# pcb_v1.net
KiCad netlist of a schematic drawn in Altium Designer
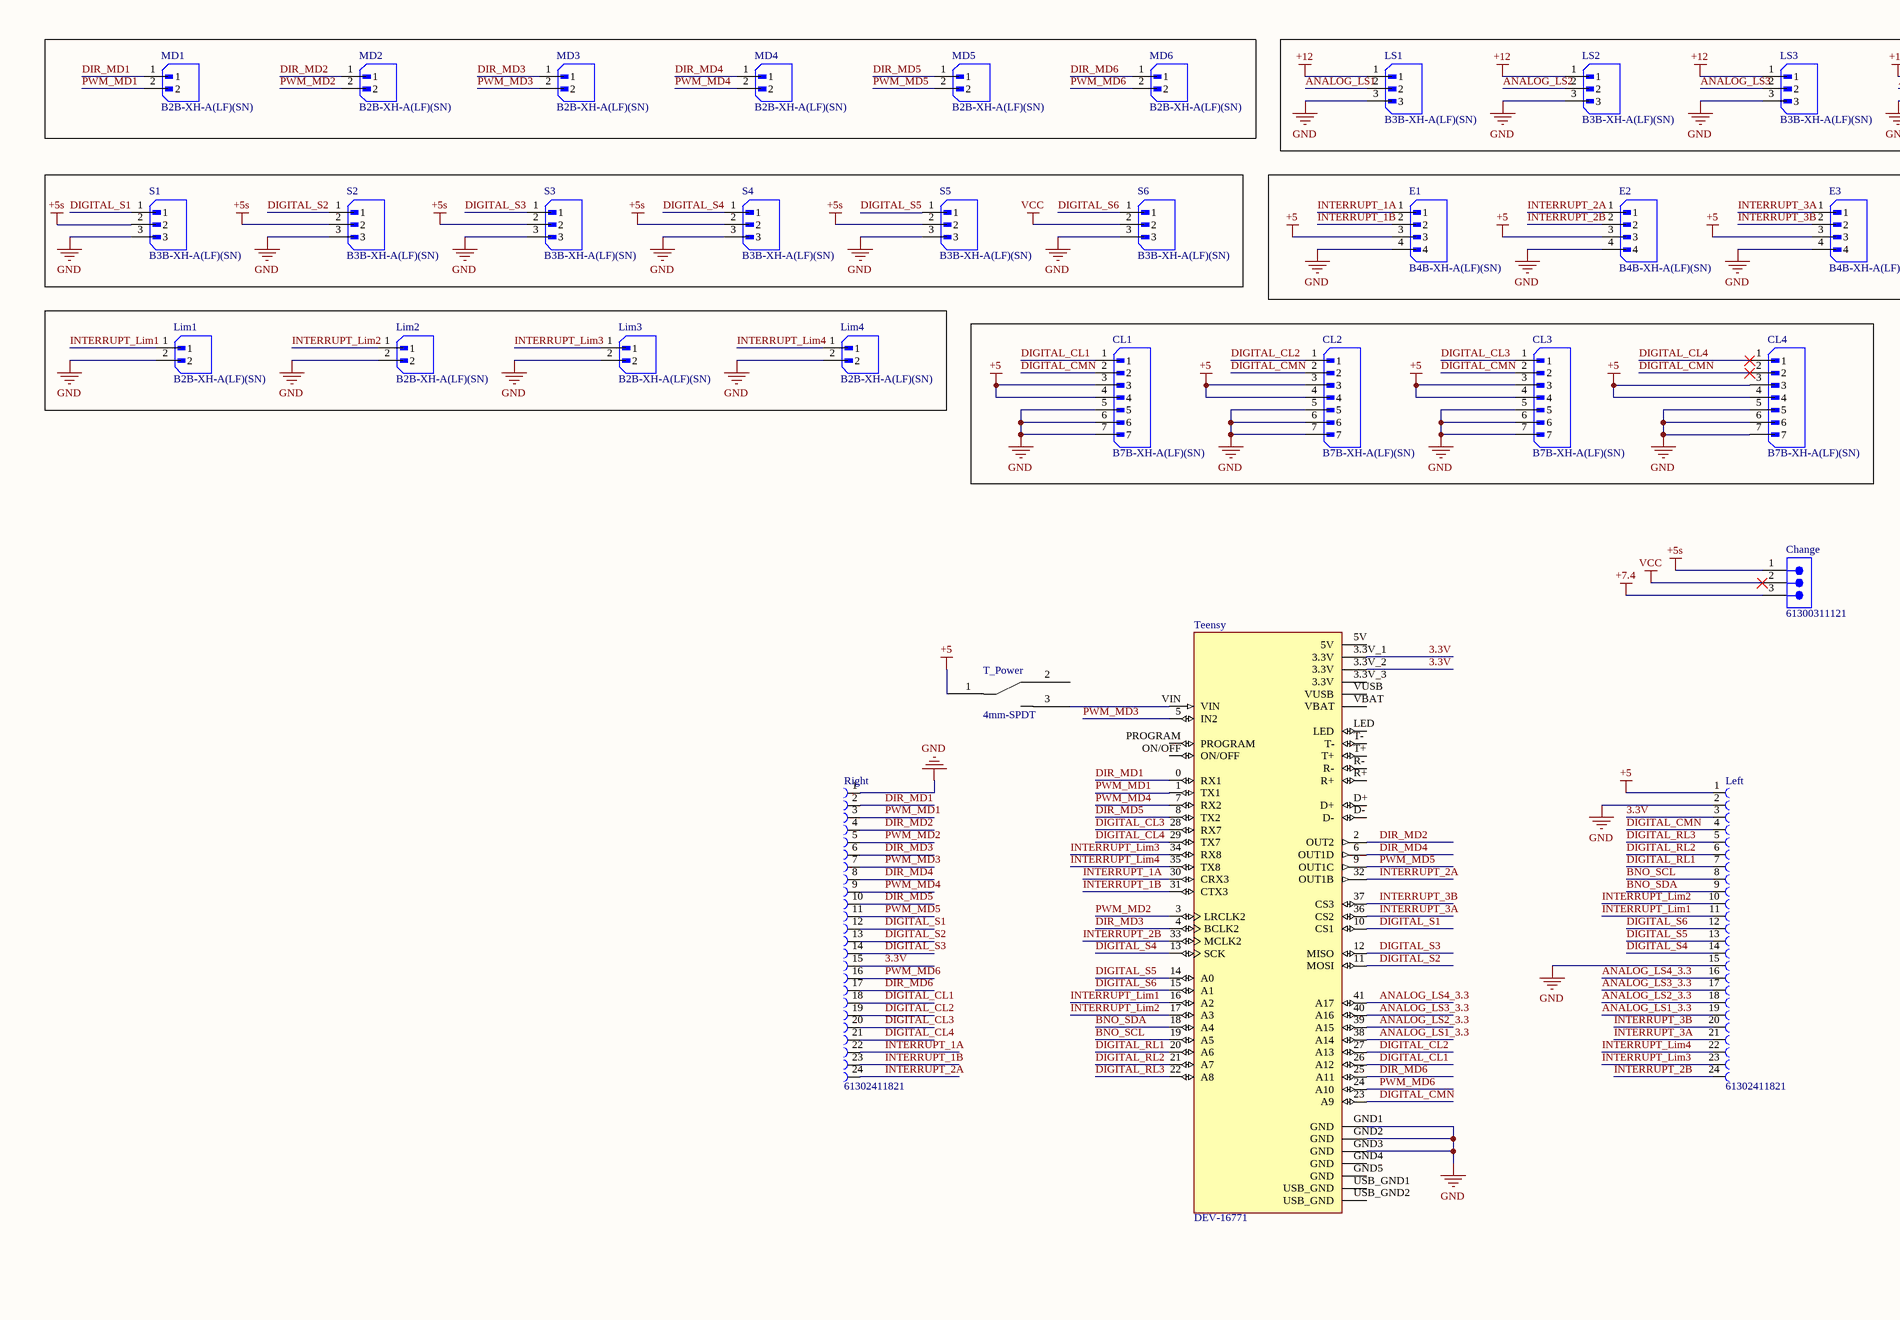
[diagram p0: pcb_v1.SchDoc, left]
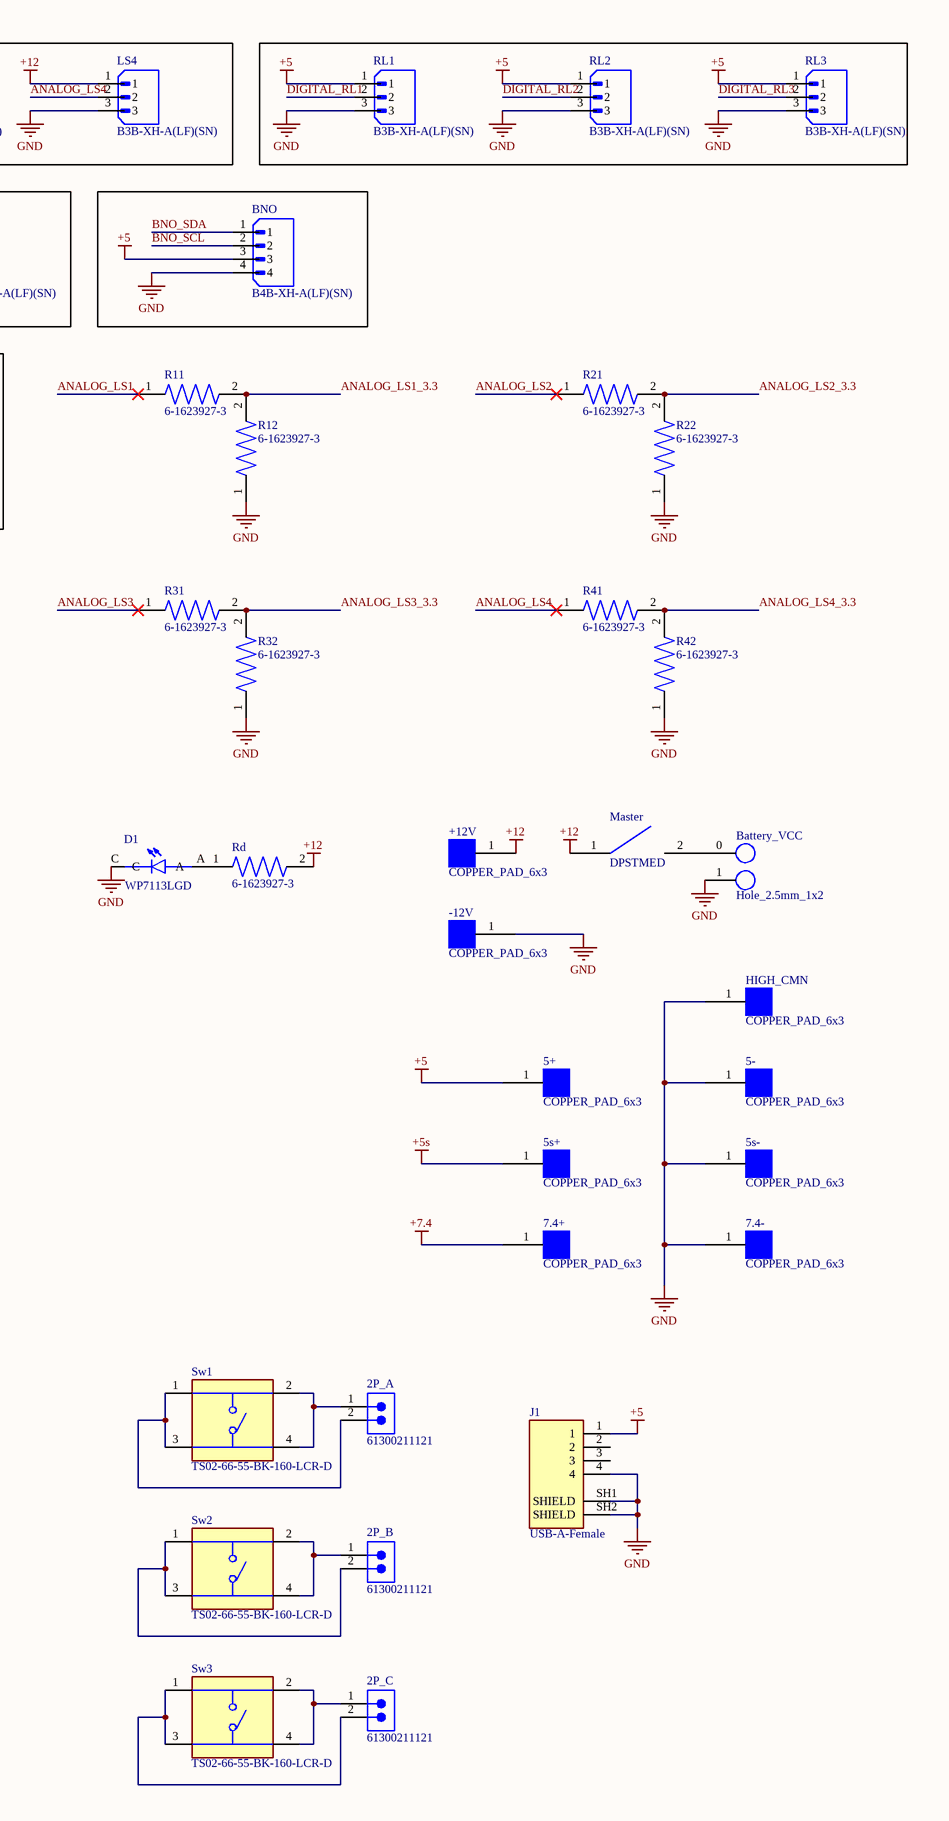
[diagram p1: pcb_v1.SchDoc, right]

(export (version "E")
  (design (tool "Eeschema 10.0.6"))
  (components
    (comp (ref "+12V")
      (value "COPPER_PAD_6x3")
      (footprint "COPPER_PAD-Footprint-1")
      (description "Exposed 6mmx3mm copper pad for soldering wires directly onto PCBs")
      (libsource (lib "") (part "COPPER_PAD-Symbol-1_1"))
    )
    (comp (ref "-12V")
      (value "COPPER_PAD_6x3")
      (footprint "COPPER_PAD-Footprint-1")
      (description "Exposed 6mmx3mm copper pad for soldering wires directly onto PCBs")
      (libsource (lib "") (part "COPPER_PAD-Symbol-1_1"))
    )
    (comp (ref "2P_A")
      (value "61300211121")
      (footprint "61300211121")
      (description "THT Vertical Pin Header WR-PHD, Pitch 2.54 mm, Single Row, 2 pins")
      (libsource (lib "CSD Robocon Workspace") (part "Header_Male_1R_02P"))
    )
    (comp (ref "2P_B")
      (value "61300211121")
      (footprint "61300211121")
      (description "THT Vertical Pin Header WR-PHD, Pitch 2.54 mm, Single Row, 2 pins")
      (libsource (lib "CSD Robocon Workspace") (part "Header_Male_1R_02P"))
    )
    (comp (ref "2P_C")
      (value "61300211121")
      (footprint "61300211121")
      (description "THT Vertical Pin Header WR-PHD, Pitch 2.54 mm, Single Row, 2 pins")
      (libsource (lib "CSD Robocon Workspace") (part "Header_Male_1R_02P"))
    )
    (comp (ref "5+")
      (value "COPPER_PAD_6x3")
      (footprint "COPPER_PAD-Footprint-1")
      (description "Exposed 6mmx3mm copper pad for soldering wires directly onto PCBs")
      (libsource (lib "CSD Robocon Workspace") (part "COPPER_PAD-Symbol-1"))
    )
    (comp (ref "5-")
      (value "COPPER_PAD_6x3")
      (footprint "COPPER_PAD-Footprint-1")
      (description "Exposed 6mmx3mm copper pad for soldering wires directly onto PCBs")
      (libsource (lib "CSD Robocon Workspace") (part "COPPER_PAD-Symbol-1"))
    )
    (comp (ref "5s+")
      (value "COPPER_PAD_6x3")
      (footprint "COPPER_PAD-Footprint-1")
      (description "Exposed 6mmx3mm copper pad for soldering wires directly onto PCBs")
      (libsource (lib "CSD Robocon Workspace") (part "COPPER_PAD-Symbol-1"))
    )
    (comp (ref "5s-")
      (value "COPPER_PAD_6x3")
      (footprint "COPPER_PAD-Footprint-1")
      (description "Exposed 6mmx3mm copper pad for soldering wires directly onto PCBs")
      (libsource (lib "CSD Robocon Workspace") (part "COPPER_PAD-Symbol-1"))
    )
    (comp (ref "7.4+")
      (value "COPPER_PAD_6x3")
      (footprint "COPPER_PAD-Footprint-1")
      (description "Exposed 6mmx3mm copper pad for soldering wires directly onto PCBs")
      (libsource (lib "CSD Robocon Workspace") (part "COPPER_PAD-Symbol-1"))
    )
    (comp (ref "7.4-")
      (value "COPPER_PAD_6x3")
      (footprint "COPPER_PAD-Footprint-1")
      (description "Exposed 6mmx3mm copper pad for soldering wires directly onto PCBs")
      (libsource (lib "CSD Robocon Workspace") (part "COPPER_PAD-Symbol-1"))
    )
    (comp (ref "Battery_VCC")
      (value "Hole_2.5mm_1x2")
      (footprint "Hole_2.5mm_1x2-Footprint-1")
      (description "2.5mm radius hole for wiring")
      (libsource (lib "CSD Robocon Workspace") (part "Hole_2.5mm_1x2-Symbol-1"))
    )
    (comp (ref "BNO")
      (value "B4B-XH-A(LF)(SN)")
      (footprint "JST_B4B-XH-A(LF)(SN)")
      (description "Connector Header Through Hole 4 position 0.098 (2.50mm)")
      (fields (field (name "MF") "JST Sales"))
      (libsource (lib "CSD Robocon Workspace") (part "B4B-XH-A(LF)(SN)"))
    )
    (comp (ref "Change")
      (value "61300311121")
      (footprint "61300311121")
      (description "THT Vertical Pin Header WR-PHD, Pitch 2.54 mm, Single Row, 3 pins")
      (libsource (lib "CSD Robocon Workspace") (part "Header_Male_1R_03P"))
    )
    (comp (ref "CL1")
      (value "B7B-XH-A(LF)(SN)")
      (footprint "JST_B7B-XH-A(LF)(SN)")
      (description "Connector Header Through Hole 7 position 0.098 (2.50mm)")
      (fields (field (name "MF") "JST Sales") (field (name "MP") "B7B-XH-A (LF)(SN)"))
      (libsource (lib "CSD Robocon Workspace") (part "B7B-XH-A(LF)(SN)"))
    )
    (comp (ref "CL2")
      (value "B7B-XH-A(LF)(SN)")
      (footprint "JST_B7B-XH-A(LF)(SN)")
      (description "Connector Header Through Hole 7 position 0.098 (2.50mm)")
      (fields (field (name "MF") "JST Sales") (field (name "MP") "B7B-XH-A (LF)(SN)"))
      (libsource (lib "CSD Robocon Workspace") (part "B7B-XH-A(LF)(SN)"))
    )
    (comp (ref "CL3")
      (value "B7B-XH-A(LF)(SN)")
      (footprint "JST_B7B-XH-A(LF)(SN)")
      (description "Connector Header Through Hole 7 position 0.098 (2.50mm)")
      (fields (field (name "MF") "JST Sales") (field (name "MP") "B7B-XH-A (LF)(SN)"))
      (libsource (lib "CSD Robocon Workspace") (part "B7B-XH-A(LF)(SN)"))
    )
    (comp (ref "CL4")
      (value "B7B-XH-A(LF)(SN)")
      (footprint "JST_B7B-XH-A(LF)(SN)")
      (description "Connector Header Through Hole 7 position 0.098 (2.50mm)")
      (fields (field (name "MF") "JST Sales") (field (name "MP") "B7B-XH-A (LF)(SN)"))
      (libsource (lib "CSD Robocon Workspace") (part "B7B-XH-A(LF)(SN)"))
    )
    (comp (ref "D1")
      (value "WP7113LGD")
      (footprint "LED_WP7113LGD")
      (description "Green 568nm LED Indication - Discrete 1.9V Radial")
      (fields (field (name "MF") "Kingbright"))
      (libsource (lib "CSD Robocon Workspace") (part "WP7113LGD"))
    )
    (comp (ref "E1")
      (value "B4B-XH-A(LF)(SN)")
      (footprint "JST_B4B-XH-A(LF)(SN)")
      (description "Connector Header Through Hole 4 position 0.098 (2.50mm)")
      (fields (field (name "MF") "JST Sales"))
      (libsource (lib "CSD Robocon Workspace") (part "B4B-XH-A(LF)(SN)"))
    )
    (comp (ref "E2")
      (value "B4B-XH-A(LF)(SN)")
      (footprint "JST_B4B-XH-A(LF)(SN)")
      (description "Connector Header Through Hole 4 position 0.098 (2.50mm)")
      (fields (field (name "MF") "JST Sales"))
      (libsource (lib "CSD Robocon Workspace") (part "B4B-XH-A(LF)(SN)"))
    )
    (comp (ref "E3")
      (value "B4B-XH-A(LF)(SN)")
      (footprint "JST_B4B-XH-A(LF)(SN)")
      (description "Connector Header Through Hole 4 position 0.098 (2.50mm)")
      (fields (field (name "MF") "JST Sales"))
      (libsource (lib "CSD Robocon Workspace") (part "B4B-XH-A(LF)(SN)"))
    )
    (comp (ref "HIGH_CMN")
      (value "COPPER_PAD_6x3")
      (footprint "COPPER_PAD-Footprint-1")
      (description "Exposed 6mmx3mm copper pad for soldering wires directly onto PCBs")
      (libsource (lib "CSD Robocon Workspace") (part "COPPER_PAD-Symbol-1"))
    )
    (comp (ref "J1")
      (value "USB-A-Female")
      (footprint "CUI_UJ2-AH-4-TH")
      (description "Type A, USB 2.0, 1 A, Right Angle, Through Hole, USB Receptacle")
      (fields (field (name "MF") "CUI Devices") (field (name "MP") "UJ2-AH-4-TH"))
      (libsource (lib "CSD Robocon Workspace") (part "UJ2-AH-4-TH"))
    )
    (comp (ref "Left")
      (value "61302411821")
      (footprint "61302411821")
      (description "Single Row / Straight / Without Shroud Female header Female 24")
      (fields (field (name "MF") "WÃ¼rth Elektronik"))
      (libsource (lib "") (part "61302411821_1"))
    )
    (comp (ref "Lim1")
      (value "B2B-XH-A(LF)(SN)")
      (footprint "JST_B2B-XH-A(LF)(SN)")
      (description "Connector Header Through Hole 2 position 0.098 (2.50mm)")
      (fields (field (name "MF") "JST Sales America Inc."))
      (libsource (lib "CSD Robocon Workspace") (part "B2B-XH-A(LF)(SN)"))
    )
    (comp (ref "Lim2")
      (value "B2B-XH-A(LF)(SN)")
      (footprint "JST_B2B-XH-A(LF)(SN)")
      (description "Connector Header Through Hole 2 position 0.098 (2.50mm)")
      (fields (field (name "MF") "JST Sales America Inc."))
      (libsource (lib "CSD Robocon Workspace") (part "B2B-XH-A(LF)(SN)"))
    )
    (comp (ref "Lim3")
      (value "B2B-XH-A(LF)(SN)")
      (footprint "JST_B2B-XH-A(LF)(SN)")
      (description "Connector Header Through Hole 2 position 0.098 (2.50mm)")
      (fields (field (name "MF") "JST Sales America Inc."))
      (libsource (lib "CSD Robocon Workspace") (part "B2B-XH-A(LF)(SN)"))
    )
    (comp (ref "Lim4")
      (value "B2B-XH-A(LF)(SN)")
      (footprint "JST_B2B-XH-A(LF)(SN)")
      (description "Connector Header Through Hole 2 position 0.098 (2.50mm)")
      (fields (field (name "MF") "JST Sales America Inc."))
      (libsource (lib "CSD Robocon Workspace") (part "B2B-XH-A(LF)(SN)"))
    )
    (comp (ref "LS1")
      (value "B3B-XH-A(LF)(SN)")
      (footprint "JST_B3B-XH-A(LF)(SN)")
      (description "Connector Header Through Hole 3 position 0.098 (2.50mm)")
      (fields (field (name "MF") "JST Sales"))
      (libsource (lib "CSD Robocon Workspace") (part "B3B-XH-A(LF)(SN)"))
    )
    (comp (ref "LS2")
      (value "B3B-XH-A(LF)(SN)")
      (footprint "JST_B3B-XH-A(LF)(SN)")
      (description "Connector Header Through Hole 3 position 0.098 (2.50mm)")
      (fields (field (name "MF") "JST Sales"))
      (libsource (lib "CSD Robocon Workspace") (part "B3B-XH-A(LF)(SN)"))
    )
    (comp (ref "LS3")
      (value "B3B-XH-A(LF)(SN)")
      (footprint "JST_B3B-XH-A(LF)(SN)")
      (description "Connector Header Through Hole 3 position 0.098 (2.50mm)")
      (fields (field (name "MF") "JST Sales"))
      (libsource (lib "CSD Robocon Workspace") (part "B3B-XH-A(LF)(SN)"))
    )
    (comp (ref "LS4")
      (value "B3B-XH-A(LF)(SN)")
      (footprint "JST_B3B-XH-A(LF)(SN)")
      (description "Connector Header Through Hole 3 position 0.098 (2.50mm)")
      (fields (field (name "MF") "JST Sales"))
      (libsource (lib "CSD Robocon Workspace") (part "B3B-XH-A(LF)(SN)"))
    )
    (comp (ref "Master")
      (value "DPSTMED")
      (footprint "SPSTMED-Footprint-1")
      (description "Medium Sized DPST switch")
      (libsource (lib "CSD Robocon Workspace") (part "SPST Switch"))
    )
    (comp (ref "MD1")
      (value "B2B-XH-A(LF)(SN)")
      (footprint "JST_B2B-XH-A(LF)(SN)")
      (description "Connector Header Through Hole 2 position 0.098 (2.50mm)")
      (fields (field (name "MF") "JST Sales America Inc."))
      (libsource (lib "CSD Robocon Workspace") (part "B2B-XH-A(LF)(SN)"))
    )
    (comp (ref "MD2")
      (value "B2B-XH-A(LF)(SN)")
      (footprint "JST_B2B-XH-A(LF)(SN)")
      (description "Connector Header Through Hole 2 position 0.098 (2.50mm)")
      (fields (field (name "MF") "JST Sales America Inc."))
      (libsource (lib "CSD Robocon Workspace") (part "B2B-XH-A(LF)(SN)"))
    )
    (comp (ref "MD3")
      (value "B2B-XH-A(LF)(SN)")
      (footprint "JST_B2B-XH-A(LF)(SN)")
      (description "Connector Header Through Hole 2 position 0.098 (2.50mm)")
      (fields (field (name "MF") "JST Sales America Inc."))
      (libsource (lib "CSD Robocon Workspace") (part "B2B-XH-A(LF)(SN)"))
    )
    (comp (ref "MD4")
      (value "B2B-XH-A(LF)(SN)")
      (footprint "JST_B2B-XH-A(LF)(SN)")
      (description "Connector Header Through Hole 2 position 0.098 (2.50mm)")
      (fields (field (name "MF") "JST Sales America Inc."))
      (libsource (lib "CSD Robocon Workspace") (part "B2B-XH-A(LF)(SN)"))
    )
    (comp (ref "MD5")
      (value "B2B-XH-A(LF)(SN)")
      (footprint "JST_B2B-XH-A(LF)(SN)")
      (description "Connector Header Through Hole 2 position 0.098 (2.50mm)")
      (fields (field (name "MF") "JST Sales America Inc."))
      (libsource (lib "CSD Robocon Workspace") (part "B2B-XH-A(LF)(SN)"))
    )
    (comp (ref "MD6")
      (value "B2B-XH-A(LF)(SN)")
      (footprint "JST_B2B-XH-A(LF)(SN)")
      (description "Connector Header Through Hole 2 position 0.098 (2.50mm)")
      (fields (field (name "MF") "JST Sales America Inc."))
      (libsource (lib "CSD Robocon Workspace") (part "B2B-XH-A(LF)(SN)"))
    )
    (comp (ref "R11")
      (value "6-1623927-3")
      (footprint "RESAD700W45L350D185")
      (description "CFR16 5% 10K")
      (libsource (lib "CSD Robocon Workspace") (part "6-1623927-3"))
    )
    (comp (ref "R12")
      (value "6-1623927-3")
      (footprint "RESAD700W45L350D185")
      (description "CFR16 5% 10K")
      (libsource (lib "CSD Robocon Workspace") (part "6-1623927-3"))
    )
    (comp (ref "R21")
      (value "6-1623927-3")
      (footprint "RESAD700W45L350D185")
      (description "CFR16 5% 10K")
      (libsource (lib "CSD Robocon Workspace") (part "6-1623927-3"))
    )
    (comp (ref "R22")
      (value "6-1623927-3")
      (footprint "RESAD700W45L350D185")
      (description "CFR16 5% 10K")
      (libsource (lib "CSD Robocon Workspace") (part "6-1623927-3"))
    )
    (comp (ref "R31")
      (value "6-1623927-3")
      (footprint "RESAD700W45L350D185")
      (description "CFR16 5% 10K")
      (libsource (lib "CSD Robocon Workspace") (part "6-1623927-3"))
    )
    (comp (ref "R32")
      (value "6-1623927-3")
      (footprint "RESAD700W45L350D185")
      (description "CFR16 5% 10K")
      (libsource (lib "CSD Robocon Workspace") (part "6-1623927-3"))
    )
    (comp (ref "R41")
      (value "6-1623927-3")
      (footprint "RESAD700W45L350D185")
      (description "CFR16 5% 10K")
      (libsource (lib "CSD Robocon Workspace") (part "6-1623927-3"))
    )
    (comp (ref "R42")
      (value "6-1623927-3")
      (footprint "RESAD700W45L350D185")
      (description "CFR16 5% 10K")
      (libsource (lib "CSD Robocon Workspace") (part "6-1623927-3"))
    )
    (comp (ref "Rd")
      (value "6-1623927-3")
      (footprint "RESAD700W45L350D185")
      (description "CFR16 5% 10K")
      (libsource (lib "CSD Robocon Workspace") (part "6-1623927-3"))
    )
    (comp (ref "Right")
      (value "61302411821")
      (footprint "61302411821")
      (description "Single Row / Straight / Without Shroud Female header Female 24")
      (fields (field (name "MF") "WÃ¼rth Elektronik"))
      (libsource (lib "CSD Robocon Workspace") (part "61302411821"))
    )
    (comp (ref "RL1")
      (value "B3B-XH-A(LF)(SN)")
      (footprint "JST_B3B-XH-A(LF)(SN)")
      (description "Connector Header Through Hole 3 position 0.098 (2.50mm)")
      (fields (field (name "MF") "JST Sales"))
      (libsource (lib "CSD Robocon Workspace") (part "B3B-XH-A(LF)(SN)"))
    )
    (comp (ref "RL2")
      (value "B3B-XH-A(LF)(SN)")
      (footprint "JST_B3B-XH-A(LF)(SN)")
      (description "Connector Header Through Hole 3 position 0.098 (2.50mm)")
      (fields (field (name "MF") "JST Sales"))
      (libsource (lib "CSD Robocon Workspace") (part "B3B-XH-A(LF)(SN)"))
    )
    (comp (ref "RL3")
      (value "B3B-XH-A(LF)(SN)")
      (footprint "JST_B3B-XH-A(LF)(SN)")
      (description "Connector Header Through Hole 3 position 0.098 (2.50mm)")
      (fields (field (name "MF") "JST Sales"))
      (libsource (lib "CSD Robocon Workspace") (part "B3B-XH-A(LF)(SN)"))
    )
    (comp (ref "S1")
      (value "B3B-XH-A(LF)(SN)")
      (footprint "JST_B3B-XH-A(LF)(SN)")
      (description "Connector Header Through Hole 3 position 0.098 (2.50mm)")
      (fields (field (name "MF") "JST Sales"))
      (libsource (lib "CSD Robocon Workspace") (part "B3B-XH-A(LF)(SN)"))
    )
    (comp (ref "S2")
      (value "B3B-XH-A(LF)(SN)")
      (footprint "JST_B3B-XH-A(LF)(SN)")
      (description "Connector Header Through Hole 3 position 0.098 (2.50mm)")
      (fields (field (name "MF") "JST Sales"))
      (libsource (lib "CSD Robocon Workspace") (part "B3B-XH-A(LF)(SN)"))
    )
    (comp (ref "S3")
      (value "B3B-XH-A(LF)(SN)")
      (footprint "JST_B3B-XH-A(LF)(SN)")
      (description "Connector Header Through Hole 3 position 0.098 (2.50mm)")
      (fields (field (name "MF") "JST Sales"))
      (libsource (lib "CSD Robocon Workspace") (part "B3B-XH-A(LF)(SN)"))
    )
    (comp (ref "S4")
      (value "B3B-XH-A(LF)(SN)")
      (footprint "JST_B3B-XH-A(LF)(SN)")
      (description "Connector Header Through Hole 3 position 0.098 (2.50mm)")
      (fields (field (name "MF") "JST Sales"))
      (libsource (lib "CSD Robocon Workspace") (part "B3B-XH-A(LF)(SN)"))
    )
    (comp (ref "S5")
      (value "B3B-XH-A(LF)(SN)")
      (footprint "JST_B3B-XH-A(LF)(SN)")
      (description "Connector Header Through Hole 3 position 0.098 (2.50mm)")
      (fields (field (name "MF") "JST Sales"))
      (libsource (lib "CSD Robocon Workspace") (part "B3B-XH-A(LF)(SN)"))
    )
    (comp (ref "S6")
      (value "B3B-XH-A(LF)(SN)")
      (footprint "JST_B3B-XH-A(LF)(SN)")
      (description "Connector Header Through Hole 3 position 0.098 (2.50mm)")
      (fields (field (name "MF") "JST Sales"))
      (libsource (lib "CSD Robocon Workspace") (part "B3B-XH-A(LF)(SN)"))
    )
    (comp (ref "Sw1")
      (value "TS02-66-55-BK-160-LCR-D")
      (footprint "SW_TS02-66-55-BK-160-LCR-D")
      (libsource (lib "CSD Robocon Workspace") (part "TS02-66-55-BK-160-LCR-D"))
    )
    (comp (ref "Sw2")
      (value "TS02-66-55-BK-160-LCR-D")
      (footprint "SW_TS02-66-55-BK-160-LCR-D")
      (libsource (lib "CSD Robocon Workspace") (part "TS02-66-55-BK-160-LCR-D"))
    )
    (comp (ref "Sw3")
      (value "TS02-66-55-BK-160-LCR-D")
      (footprint "SW_TS02-66-55-BK-160-LCR-D")
      (libsource (lib "CSD Robocon Workspace") (part "TS02-66-55-BK-160-LCR-D"))
    )
    (comp (ref "Teensy")
      (value "DEV-16771")
      (footprint "MODULE_DEV-16771")
      (description "RT1062 Teensy 4.1 series ARMÂ® CortexÂ®-M7 MPU Embedded Evaluation Board")
      (fields (field (name "MF") "SparkFun Electronics"))
      (libsource (lib "CSD Robocon Workspace") (part "DEV-16771"))
    )
    (comp (ref "T_Power")
      (value "4mm-SPDT")
      (footprint "4mm-SPDT-Footprint-1")
      (description "4mm Single Pole Double Throw Switch")
      (libsource (lib "CSD Robocon Workspace") (part "4mm-SPDT-Symbol-1"))
    )
  )
  (nets
    (net (code "1") (name "+5") (class "Default")
      (node (ref "5+") (pin "1") (pinfunction "3_1") (pintype "passive"))
      (node (ref "BNO") (pin "3") (pinfunction "3_3") (pintype "passive"))
      (node (ref "CL1") (pin "3") (pinfunction "3_3") (pintype "passive"))
      (node (ref "CL1") (pin "4") (pinfunction "4_4") (pintype "passive"))
      (node (ref "CL2") (pin "3") (pinfunction "3_3") (pintype "passive"))
      (node (ref "CL2") (pin "4") (pinfunction "4_4") (pintype "passive"))
      (node (ref "CL3") (pin "3") (pinfunction "3_3") (pintype "passive"))
      (node (ref "CL3") (pin "4") (pinfunction "4_4") (pintype "passive"))
      (node (ref "CL4") (pin "3") (pinfunction "3_3") (pintype "passive"))
      (node (ref "CL4") (pin "4") (pinfunction "4_4") (pintype "passive"))
      (node (ref "E1") (pin "3") (pinfunction "3_3") (pintype "passive"))
      (node (ref "E2") (pin "3") (pinfunction "3_3") (pintype "passive"))
      (node (ref "E3") (pin "3") (pinfunction "3_3") (pintype "passive"))
      (node (ref "J1") (pin "1") (pinfunction "1_1") (pintype "passive"))
      (node (ref "Left") (pin "1") (pinfunction "1_1") (pintype "passive"))
      (node (ref "RL1") (pin "1") (pinfunction "1_1") (pintype "passive"))
      (node (ref "RL2") (pin "1") (pinfunction "1_1") (pintype "passive"))
      (node (ref "RL3") (pin "1") (pinfunction "1_1") (pintype "passive"))
      (node (ref "T_Power") (pin "1") (pinfunction "1_1") (pintype "passive"))
    )
    (net (code "2") (name "+5s") (class "Default")
      (node (ref "5s+") (pin "1") (pinfunction "3_1") (pintype "passive"))
      (node (ref "Change") (pin "1") (pinfunction "1_1") (pintype "passive"))
      (node (ref "S1") (pin "2") (pinfunction "2_2") (pintype "passive"))
      (node (ref "S2") (pin "2") (pinfunction "2_2") (pintype "passive"))
      (node (ref "S3") (pin "2") (pinfunction "2_2") (pintype "passive"))
      (node (ref "S4") (pin "2") (pinfunction "2_2") (pintype "passive"))
      (node (ref "S5") (pin "2") (pinfunction "2_2") (pintype "passive"))
    )
    (net (code "3") (name "+7.4") (class "Default")
      (node (ref "7.4+") (pin "1") (pinfunction "3_1") (pintype "passive"))
      (node (ref "Change") (pin "3") (pinfunction "3_3") (pintype "passive"))
    )
    (net (code "4") (name "+12") (class "Default")
      (node (ref "+12V") (pin "1") (pinfunction "3_1") (pintype "passive"))
      (node (ref "LS1") (pin "1") (pinfunction "1_1") (pintype "passive"))
      (node (ref "LS2") (pin "1") (pinfunction "1_1") (pintype "passive"))
      (node (ref "LS3") (pin "1") (pinfunction "1_1") (pintype "passive"))
      (node (ref "LS4") (pin "1") (pinfunction "1_1") (pintype "passive"))
      (node (ref "Master") (pin "1") (pinfunction "1_1") (pintype "passive"))
      (node (ref "Rd") (pin "2") (pinfunction "2_2") (pintype "passive"))
    )
    (net (code "5") (name "/3.3V") (class "Default")
      (node (ref "Left") (pin "3") (pinfunction "3_3") (pintype "passive"))
      (node (ref "Right") (pin "15") (pinfunction "15_15") (pintype "passive"))
      (node (ref "Teensy") (pin "3.3V_1") (pinfunction "3.3V_3.3V_1") (pintype "power_in"))
      (node (ref "Teensy") (pin "3.3V_2") (pinfunction "3.3V_3.3V_2") (pintype "power_in"))
    )
    (net (code "6") (name "/ANALOG_LS1") (class "Default")
      (node (ref "LS1") (pin "2") (pinfunction "2_2") (pintype "passive"))
      (node (ref "R11") (pin "1") (pinfunction "1_1") (pintype "passive"))
    )
    (net (code "7") (name "/ANALOG_LS1_3.3") (class "Default")
      (node (ref "Left") (pin "19") (pinfunction "19_19") (pintype "passive"))
      (node (ref "R11") (pin "2") (pinfunction "2_2") (pintype "passive"))
      (node (ref "R12") (pin "2") (pinfunction "2_2") (pintype "passive"))
      (node (ref "Teensy") (pin "38") (pinfunction "A14_38") (pintype "bidirectional"))
    )
    (net (code "8") (name "/ANALOG_LS2") (class "Default")
      (node (ref "LS2") (pin "2") (pinfunction "2_2") (pintype "passive"))
      (node (ref "R21") (pin "1") (pinfunction "1_1") (pintype "passive"))
    )
    (net (code "9") (name "/ANALOG_LS2_3.3") (class "Default")
      (node (ref "Left") (pin "18") (pinfunction "18_18") (pintype "passive"))
      (node (ref "R21") (pin "2") (pinfunction "2_2") (pintype "passive"))
      (node (ref "R22") (pin "2") (pinfunction "2_2") (pintype "passive"))
      (node (ref "Teensy") (pin "39") (pinfunction "A15_39") (pintype "bidirectional"))
    )
    (net (code "10") (name "/ANALOG_LS3") (class "Default")
      (node (ref "LS3") (pin "2") (pinfunction "2_2") (pintype "passive"))
      (node (ref "R31") (pin "1") (pinfunction "1_1") (pintype "passive"))
    )
    (net (code "11") (name "/ANALOG_LS3_3.3") (class "Default")
      (node (ref "Left") (pin "17") (pinfunction "17_17") (pintype "passive"))
      (node (ref "R31") (pin "2") (pinfunction "2_2") (pintype "passive"))
      (node (ref "R32") (pin "2") (pinfunction "2_2") (pintype "passive"))
      (node (ref "Teensy") (pin "40") (pinfunction "A16_40") (pintype "bidirectional"))
    )
    (net (code "12") (name "/ANALOG_LS4") (class "Default")
      (node (ref "LS4") (pin "2") (pinfunction "2_2") (pintype "passive"))
      (node (ref "R41") (pin "1") (pinfunction "1_1") (pintype "passive"))
    )
    (net (code "13") (name "/ANALOG_LS4_3.3") (class "Default")
      (node (ref "Left") (pin "16") (pinfunction "16_16") (pintype "passive"))
      (node (ref "R41") (pin "2") (pinfunction "2_2") (pintype "passive"))
      (node (ref "R42") (pin "2") (pinfunction "2_2") (pintype "passive"))
      (node (ref "Teensy") (pin "41") (pinfunction "A17_41") (pintype "bidirectional"))
    )
    (net (code "14") (name "/BNO_SCL") (class "Default")
      (node (ref "BNO") (pin "2") (pinfunction "2_2") (pintype "passive"))
      (node (ref "Left") (pin "8") (pinfunction "8_8") (pintype "passive"))
      (node (ref "Teensy") (pin "19") (pinfunction "A5_19") (pintype "bidirectional"))
    )
    (net (code "15") (name "/BNO_SDA") (class "Default")
      (node (ref "BNO") (pin "1") (pinfunction "1_1") (pintype "passive"))
      (node (ref "Left") (pin "9") (pinfunction "9_9") (pintype "passive"))
      (node (ref "Teensy") (pin "18") (pinfunction "A4_18") (pintype "bidirectional"))
    )
    (net (code "16") (name "/DIGITAL_CL1") (class "Default")
      (node (ref "CL1") (pin "1") (pinfunction "1_1") (pintype "passive"))
      (node (ref "Right") (pin "18") (pinfunction "18_18") (pintype "passive"))
      (node (ref "Teensy") (pin "26") (pinfunction "A12_26") (pintype "bidirectional"))
    )
    (net (code "17") (name "/DIGITAL_CL2") (class "Default")
      (node (ref "CL2") (pin "1") (pinfunction "1_1") (pintype "passive"))
      (node (ref "Right") (pin "19") (pinfunction "19_19") (pintype "passive"))
      (node (ref "Teensy") (pin "27") (pinfunction "A13_27") (pintype "bidirectional"))
    )
    (net (code "18") (name "/DIGITAL_CL3") (class "Default")
      (node (ref "CL3") (pin "1") (pinfunction "1_1") (pintype "passive"))
      (node (ref "Right") (pin "20") (pinfunction "20_20") (pintype "passive"))
      (node (ref "Teensy") (pin "28") (pinfunction "RX7_28") (pintype "bidirectional"))
    )
    (net (code "19") (name "/DIGITAL_CL4") (class "Default")
      (node (ref "CL4") (pin "1") (pinfunction "1_1") (pintype "passive"))
      (node (ref "Right") (pin "21") (pinfunction "21_21") (pintype "passive"))
      (node (ref "Teensy") (pin "29") (pinfunction "TX7_29") (pintype "bidirectional"))
    )
    (net (code "20") (name "/DIGITAL_CMN") (class "Default")
      (node (ref "CL1") (pin "2") (pinfunction "2_2") (pintype "passive"))
      (node (ref "CL2") (pin "2") (pinfunction "2_2") (pintype "passive"))
      (node (ref "CL3") (pin "2") (pinfunction "2_2") (pintype "passive"))
      (node (ref "CL4") (pin "2") (pinfunction "2_2") (pintype "passive"))
      (node (ref "Left") (pin "4") (pinfunction "4_4") (pintype "passive"))
      (node (ref "Teensy") (pin "23") (pinfunction "A9_23") (pintype "bidirectional"))
    )
    (net (code "21") (name "/DIGITAL_RL1") (class "Default")
      (node (ref "Left") (pin "7") (pinfunction "7_7") (pintype "passive"))
      (node (ref "RL1") (pin "2") (pinfunction "2_2") (pintype "passive"))
      (node (ref "Teensy") (pin "20") (pinfunction "A6_20") (pintype "bidirectional"))
    )
    (net (code "22") (name "/DIGITAL_RL2") (class "Default")
      (node (ref "Left") (pin "6") (pinfunction "6_6") (pintype "passive"))
      (node (ref "RL2") (pin "2") (pinfunction "2_2") (pintype "passive"))
      (node (ref "Teensy") (pin "21") (pinfunction "A7_21") (pintype "bidirectional"))
    )
    (net (code "23") (name "/DIGITAL_RL3") (class "Default")
      (node (ref "Left") (pin "5") (pinfunction "5_5") (pintype "passive"))
      (node (ref "RL3") (pin "2") (pinfunction "2_2") (pintype "passive"))
      (node (ref "Teensy") (pin "22") (pinfunction "A8_22") (pintype "bidirectional"))
    )
    (net (code "24") (name "/DIGITAL_S1") (class "Default")
      (node (ref "Right") (pin "12") (pinfunction "12_12") (pintype "passive"))
      (node (ref "S1") (pin "1") (pinfunction "1_1") (pintype "passive"))
      (node (ref "Teensy") (pin "10") (pinfunction "CS1_10") (pintype "bidirectional"))
    )
    (net (code "25") (name "/DIGITAL_S2") (class "Default")
      (node (ref "Right") (pin "13") (pinfunction "13_13") (pintype "passive"))
      (node (ref "S2") (pin "1") (pinfunction "1_1") (pintype "passive"))
      (node (ref "Teensy") (pin "11") (pinfunction "MOSI_11") (pintype "bidirectional"))
    )
    (net (code "26") (name "/DIGITAL_S3") (class "Default")
      (node (ref "Right") (pin "14") (pinfunction "14_14") (pintype "passive"))
      (node (ref "S3") (pin "1") (pinfunction "1_1") (pintype "passive"))
      (node (ref "Teensy") (pin "12") (pinfunction "MISO_12") (pintype "bidirectional"))
    )
    (net (code "27") (name "/DIGITAL_S4") (class "Default")
      (node (ref "Left") (pin "14") (pinfunction "14_14") (pintype "passive"))
      (node (ref "S4") (pin "1") (pinfunction "1_1") (pintype "passive"))
      (node (ref "Teensy") (pin "13") (pinfunction "SCK_13") (pintype "bidirectional"))
    )
    (net (code "28") (name "/DIGITAL_S5") (class "Default")
      (node (ref "Left") (pin "13") (pinfunction "13_13") (pintype "passive"))
      (node (ref "S5") (pin "1") (pinfunction "1_1") (pintype "passive"))
      (node (ref "Teensy") (pin "14") (pinfunction "A0_14") (pintype "bidirectional"))
    )
    (net (code "29") (name "/DIGITAL_S6") (class "Default")
      (node (ref "Left") (pin "12") (pinfunction "12_12") (pintype "passive"))
      (node (ref "S6") (pin "1") (pinfunction "1_1") (pintype "passive"))
      (node (ref "Teensy") (pin "15") (pinfunction "A1_15") (pintype "bidirectional"))
    )
    (net (code "30") (name "/DIR_MD1") (class "Default")
      (node (ref "MD1") (pin "1") (pinfunction "1_1") (pintype "passive"))
      (node (ref "Right") (pin "2") (pinfunction "2_2") (pintype "passive"))
      (node (ref "Teensy") (pin "0") (pinfunction "RX1_0") (pintype "bidirectional"))
    )
    (net (code "31") (name "/DIR_MD2") (class "Default")
      (node (ref "MD2") (pin "1") (pinfunction "1_1") (pintype "passive"))
      (node (ref "Right") (pin "4") (pinfunction "4_4") (pintype "passive"))
      (node (ref "Teensy") (pin "2") (pinfunction "OUT2_2") (pintype "output"))
    )
    (net (code "32") (name "/DIR_MD3") (class "Default")
      (node (ref "MD3") (pin "1") (pinfunction "1_1") (pintype "passive"))
      (node (ref "Right") (pin "6") (pinfunction "6_6") (pintype "passive"))
      (node (ref "Teensy") (pin "4") (pinfunction "BCLK2_4") (pintype "bidirectional"))
    )
    (net (code "33") (name "/DIR_MD4") (class "Default")
      (node (ref "MD4") (pin "1") (pinfunction "1_1") (pintype "passive"))
      (node (ref "Right") (pin "8") (pinfunction "8_8") (pintype "passive"))
      (node (ref "Teensy") (pin "6") (pinfunction "OUT1D_6") (pintype "output"))
    )
    (net (code "34") (name "/DIR_MD5") (class "Default")
      (node (ref "MD5") (pin "1") (pinfunction "1_1") (pintype "passive"))
      (node (ref "Right") (pin "10") (pinfunction "10_10") (pintype "passive"))
      (node (ref "Teensy") (pin "8") (pinfunction "TX2_8") (pintype "bidirectional"))
    )
    (net (code "35") (name "/DIR_MD6") (class "Default")
      (node (ref "MD6") (pin "1") (pinfunction "1_1") (pintype "passive"))
      (node (ref "Right") (pin "17") (pinfunction "17_17") (pintype "passive"))
      (node (ref "Teensy") (pin "25") (pinfunction "A11_25") (pintype "bidirectional"))
    )
    (net (code "36") (name "/INTERRUPT_1A") (class "Default")
      (node (ref "E1") (pin "1") (pinfunction "1_1") (pintype "passive"))
      (node (ref "Right") (pin "22") (pinfunction "22_22") (pintype "passive"))
      (node (ref "Teensy") (pin "30") (pinfunction "CRX3_30") (pintype "bidirectional"))
    )
    (net (code "37") (name "/INTERRUPT_1B") (class "Default")
      (node (ref "E1") (pin "2") (pinfunction "2_2") (pintype "passive"))
      (node (ref "Right") (pin "23") (pinfunction "23_23") (pintype "passive"))
      (node (ref "Teensy") (pin "31") (pinfunction "CTX3_31") (pintype "bidirectional"))
    )
    (net (code "38") (name "/INTERRUPT_2A") (class "Default")
      (node (ref "E2") (pin "1") (pinfunction "1_1") (pintype "passive"))
      (node (ref "Right") (pin "24") (pinfunction "24_24") (pintype "passive"))
      (node (ref "Teensy") (pin "32") (pinfunction "OUT1B_32") (pintype "output"))
    )
    (net (code "39") (name "/INTERRUPT_2B") (class "Default")
      (node (ref "E2") (pin "2") (pinfunction "2_2") (pintype "passive"))
      (node (ref "Left") (pin "24") (pinfunction "24_24") (pintype "passive"))
      (node (ref "Teensy") (pin "33") (pinfunction "MCLK2_33") (pintype "bidirectional"))
    )
    (net (code "40") (name "/INTERRUPT_3A") (class "Default")
      (node (ref "E3") (pin "1") (pinfunction "1_1") (pintype "passive"))
      (node (ref "Left") (pin "21") (pinfunction "21_21") (pintype "passive"))
      (node (ref "Teensy") (pin "36") (pinfunction "CS2_36") (pintype "bidirectional"))
    )
    (net (code "41") (name "/INTERRUPT_3B") (class "Default")
      (node (ref "E3") (pin "2") (pinfunction "2_2") (pintype "passive"))
      (node (ref "Left") (pin "20") (pinfunction "20_20") (pintype "passive"))
      (node (ref "Teensy") (pin "37") (pinfunction "CS3_37") (pintype "bidirectional"))
    )
    (net (code "42") (name "/INTERRUPT_Lim1") (class "Default")
      (node (ref "Left") (pin "11") (pinfunction "11_11") (pintype "passive"))
      (node (ref "Lim1") (pin "1") (pinfunction "1_1") (pintype "passive"))
      (node (ref "Teensy") (pin "16") (pinfunction "A2_16") (pintype "bidirectional"))
    )
    (net (code "43") (name "/INTERRUPT_Lim2") (class "Default")
      (node (ref "Left") (pin "10") (pinfunction "10_10") (pintype "passive"))
      (node (ref "Lim2") (pin "1") (pinfunction "1_1") (pintype "passive"))
      (node (ref "Teensy") (pin "17") (pinfunction "A3_17") (pintype "bidirectional"))
    )
    (net (code "44") (name "/INTERRUPT_Lim3") (class "Default")
      (node (ref "Left") (pin "23") (pinfunction "23_23") (pintype "passive"))
      (node (ref "Lim3") (pin "1") (pinfunction "1_1") (pintype "passive"))
      (node (ref "Teensy") (pin "34") (pinfunction "RX8_34") (pintype "bidirectional"))
    )
    (net (code "45") (name "/INTERRUPT_Lim4") (class "Default")
      (node (ref "Left") (pin "22") (pinfunction "22_22") (pintype "passive"))
      (node (ref "Lim4") (pin "1") (pinfunction "1_1") (pintype "passive"))
      (node (ref "Teensy") (pin "35") (pinfunction "TX8_35") (pintype "bidirectional"))
    )
    (net (code "46") (name "/PWM_MD1") (class "Default")
      (node (ref "MD1") (pin "2") (pinfunction "2_2") (pintype "passive"))
      (node (ref "Right") (pin "3") (pinfunction "3_3") (pintype "passive"))
      (node (ref "Teensy") (pin "1") (pinfunction "TX1_1") (pintype "bidirectional"))
    )
    (net (code "47") (name "/PWM_MD2") (class "Default")
      (node (ref "MD2") (pin "2") (pinfunction "2_2") (pintype "passive"))
      (node (ref "Right") (pin "5") (pinfunction "5_5") (pintype "passive"))
      (node (ref "Teensy") (pin "3") (pinfunction "LRCLK2_3") (pintype "bidirectional"))
    )
    (net (code "48") (name "/PWM_MD3") (class "Default")
      (node (ref "MD3") (pin "2") (pinfunction "2_2") (pintype "passive"))
      (node (ref "Right") (pin "7") (pinfunction "7_7") (pintype "passive"))
      (node (ref "Teensy") (pin "5") (pinfunction "IN2_5") (pintype "bidirectional"))
    )
    (net (code "49") (name "/PWM_MD4") (class "Default")
      (node (ref "MD4") (pin "2") (pinfunction "2_2") (pintype "passive"))
      (node (ref "Right") (pin "9") (pinfunction "9_9") (pintype "passive"))
      (node (ref "Teensy") (pin "7") (pinfunction "RX2_7") (pintype "bidirectional"))
    )
    (net (code "50") (name "/PWM_MD5") (class "Default")
      (node (ref "MD5") (pin "2") (pinfunction "2_2") (pintype "passive"))
      (node (ref "Right") (pin "11") (pinfunction "11_11") (pintype "passive"))
      (node (ref "Teensy") (pin "9") (pinfunction "OUT1C_9") (pintype "output"))
    )
    (net (code "51") (name "/PWM_MD6") (class "Default")
      (node (ref "MD6") (pin "2") (pinfunction "2_2") (pintype "passive"))
      (node (ref "Right") (pin "16") (pinfunction "16_16") (pintype "passive"))
      (node (ref "Teensy") (pin "24") (pinfunction "A10_24") (pintype "bidirectional"))
    )
    (net (code "52") (name "GND") (class "Default")
      (node (ref "-12V") (pin "1") (pinfunction "3_1") (pintype "passive"))
      (node (ref "5-") (pin "1") (pinfunction "3_1") (pintype "passive"))
      (node (ref "5s-") (pin "1") (pinfunction "3_1") (pintype "passive"))
      (node (ref "7.4-") (pin "1") (pinfunction "3_1") (pintype "passive"))
      (node (ref "BNO") (pin "4") (pinfunction "4_4") (pintype "passive"))
      (node (ref "Battery_VCC") (pin "1") (pinfunction "1_1") (pintype "passive"))
      (node (ref "CL1") (pin "5") (pinfunction "5_5") (pintype "passive"))
      (node (ref "CL1") (pin "6") (pinfunction "6_6") (pintype "passive"))
      (node (ref "CL1") (pin "7") (pinfunction "7_7") (pintype "passive"))
      (node (ref "CL2") (pin "5") (pinfunction "5_5") (pintype "passive"))
      (node (ref "CL2") (pin "6") (pinfunction "6_6") (pintype "passive"))
      (node (ref "CL2") (pin "7") (pinfunction "7_7") (pintype "passive"))
      (node (ref "CL3") (pin "5") (pinfunction "5_5") (pintype "passive"))
      (node (ref "CL3") (pin "6") (pinfunction "6_6") (pintype "passive"))
      (node (ref "CL3") (pin "7") (pinfunction "7_7") (pintype "passive"))
      (node (ref "CL4") (pin "5") (pinfunction "5_5") (pintype "passive"))
      (node (ref "CL4") (pin "6") (pinfunction "6_6") (pintype "passive"))
      (node (ref "CL4") (pin "7") (pinfunction "7_7") (pintype "passive"))
      (node (ref "D1") (pin "C") (pinfunction "C_C") (pintype "passive"))
      (node (ref "E1") (pin "4") (pinfunction "4_4") (pintype "passive"))
      (node (ref "E2") (pin "4") (pinfunction "4_4") (pintype "passive"))
      (node (ref "E3") (pin "4") (pinfunction "4_4") (pintype "passive"))
      (node (ref "HIGH_CMN") (pin "1") (pinfunction "3_1") (pintype "passive"))
      (node (ref "J1") (pin "4") (pinfunction "4_4") (pintype "passive"))
      (node (ref "J1") (pin "SH1") (pinfunction "SHIELD_SH1") (pintype "passive"))
      (node (ref "J1") (pin "SH2") (pinfunction "SHIELD_SH2") (pintype "passive"))
      (node (ref "LS1") (pin "3") (pinfunction "3_3") (pintype "passive"))
      (node (ref "LS2") (pin "3") (pinfunction "3_3") (pintype "passive"))
      (node (ref "LS3") (pin "3") (pinfunction "3_3") (pintype "passive"))
      (node (ref "LS4") (pin "3") (pinfunction "3_3") (pintype "passive"))
      (node (ref "Left") (pin "15") (pinfunction "15_15") (pintype "passive"))
      (node (ref "Left") (pin "2") (pinfunction "2_2") (pintype "passive"))
      (node (ref "Lim1") (pin "2") (pinfunction "2_2") (pintype "passive"))
      (node (ref "Lim2") (pin "2") (pinfunction "2_2") (pintype "passive"))
      (node (ref "Lim3") (pin "2") (pinfunction "2_2") (pintype "passive"))
      (node (ref "Lim4") (pin "2") (pinfunction "2_2") (pintype "passive"))
      (node (ref "R12") (pin "1") (pinfunction "1_1") (pintype "passive"))
      (node (ref "R22") (pin "1") (pinfunction "1_1") (pintype "passive"))
      (node (ref "R32") (pin "1") (pinfunction "1_1") (pintype "passive"))
      (node (ref "R42") (pin "1") (pinfunction "1_1") (pintype "passive"))
      (node (ref "RL1") (pin "3") (pinfunction "3_3") (pintype "passive"))
      (node (ref "RL2") (pin "3") (pinfunction "3_3") (pintype "passive"))
      (node (ref "RL3") (pin "3") (pinfunction "3_3") (pintype "passive"))
      (node (ref "Right") (pin "1") (pinfunction "1_1") (pintype "passive"))
      (node (ref "S1") (pin "3") (pinfunction "3_3") (pintype "passive"))
      (node (ref "S2") (pin "3") (pinfunction "3_3") (pintype "passive"))
      (node (ref "S3") (pin "3") (pinfunction "3_3") (pintype "passive"))
      (node (ref "S4") (pin "3") (pinfunction "3_3") (pintype "passive"))
      (node (ref "S5") (pin "3") (pinfunction "3_3") (pintype "passive"))
      (node (ref "S6") (pin "3") (pinfunction "3_3") (pintype "passive"))
      (node (ref "Teensy") (pin "GND1") (pinfunction "GND_GND1") (pintype "power_in"))
      (node (ref "Teensy") (pin "GND2") (pinfunction "GND_GND2") (pintype "power_in"))
      (node (ref "Teensy") (pin "GND3") (pinfunction "GND_GND3") (pintype "power_in"))
    )
    (net (code "53") (name "Net-(2P_A-Pad1)") (class "Default")
      (node (ref "2P_A") (pin "1") (pinfunction "1_1") (pintype "passive"))
      (node (ref "Sw1") (pin "2") (pinfunction "2_2") (pintype "passive"))
      (node (ref "Sw1") (pin "4") (pinfunction "4_4") (pintype "passive"))
    )
    (net (code "54") (name "Net-(2P_A-Pad2)") (class "Default")
      (node (ref "2P_A") (pin "2") (pinfunction "2_2") (pintype "passive"))
      (node (ref "Sw1") (pin "1") (pinfunction "1_1") (pintype "passive"))
      (node (ref "Sw1") (pin "3") (pinfunction "3_3") (pintype "passive"))
    )
    (net (code "55") (name "Net-(2P_B-Pad1)") (class "Default")
      (node (ref "2P_B") (pin "1") (pinfunction "1_1") (pintype "passive"))
      (node (ref "Sw2") (pin "2") (pinfunction "2_2") (pintype "passive"))
      (node (ref "Sw2") (pin "4") (pinfunction "4_4") (pintype "passive"))
    )
    (net (code "56") (name "Net-(2P_B-Pad2)") (class "Default")
      (node (ref "2P_B") (pin "2") (pinfunction "2_2") (pintype "passive"))
      (node (ref "Sw2") (pin "1") (pinfunction "1_1") (pintype "passive"))
      (node (ref "Sw2") (pin "3") (pinfunction "3_3") (pintype "passive"))
    )
    (net (code "57") (name "Net-(2P_C-Pad1)") (class "Default")
      (node (ref "2P_C") (pin "1") (pinfunction "1_1") (pintype "passive"))
      (node (ref "Sw3") (pin "2") (pinfunction "2_2") (pintype "passive"))
      (node (ref "Sw3") (pin "4") (pinfunction "4_4") (pintype "passive"))
    )
    (net (code "58") (name "Net-(2P_C-Pad2)") (class "Default")
      (node (ref "2P_C") (pin "2") (pinfunction "2_2") (pintype "passive"))
      (node (ref "Sw3") (pin "1") (pinfunction "1_1") (pintype "passive"))
      (node (ref "Sw3") (pin "3") (pinfunction "3_3") (pintype "passive"))
    )
    (net (code "59") (name "Net-(Battery_VCC-Pad0)") (class "Default")
      (node (ref "Battery_VCC") (pin "0") (pinfunction "0_0") (pintype "passive"))
      (node (ref "Master") (pin "2") (pinfunction "2_2") (pintype "passive"))
    )
    (net (code "60") (name "Net-(D1-PadA)") (class "Default")
      (node (ref "D1") (pin "A") (pinfunction "A_A") (pintype "passive"))
      (node (ref "Rd") (pin "1") (pinfunction "1_1") (pintype "passive"))
    )
    (net (code "61") (name "Net-(T_Power-Pad3)") (class "Default")
      (node (ref "T_Power") (pin "3") (pinfunction "3_3") (pintype "passive"))
      (node (ref "Teensy") (pin "VIN") (pinfunction "VIN_VIN") (pintype "input"))
    )
    (net (code "62") (name "VCC") (class "Default")
      (node (ref "Change") (pin "2") (pinfunction "2_2") (pintype "passive"))
      (node (ref "S6") (pin "2") (pinfunction "2_2") (pintype "passive"))
    )
    (net (code "63") (name "unconnected-(J1-Pad2)") (class "Default")
      (node (ref "J1") (pin "2") (pinfunction "2_2") (pintype "passive"))
    )
    (net (code "64") (name "unconnected-(J1-Pad3)") (class "Default")
      (node (ref "J1") (pin "3") (pinfunction "3_3") (pintype "passive"))
    )
    (net (code "65") (name "unconnected-(T_Power-Pad2)") (class "Default")
      (node (ref "T_Power") (pin "2") (pinfunction "2_2") (pintype "passive"))
    )
    (net (code "66") (name "unconnected-(Teensy-3.3V-Pad3.3V_3)") (class "Default")
      (node (ref "Teensy") (pin "3.3V_3") (pinfunction "3.3V_3.3V_3") (pintype "power_in"))
    )
    (net (code "67") (name "unconnected-(Teensy-GND-PadGND4)") (class "Default")
      (node (ref "Teensy") (pin "GND4") (pinfunction "GND_GND4") (pintype "power_in"))
    )
    (net (code "68") (name "unconnected-(Teensy-GND-PadGND5)") (class "Default")
      (node (ref "Teensy") (pin "GND5") (pinfunction "GND_GND5") (pintype "power_in"))
    )
    (net (code "69") (name "unconnected-(Teensy-Pad5V)") (class "Default")
      (node (ref "Teensy") (pin "5V") (pinfunction "5V_5V") (pintype "power_in"))
    )
    (net (code "70") (name "unconnected-(Teensy-PadD+)") (class "Default")
      (node (ref "Teensy") (pin "D+") (pinfunction "D+_D+") (pintype "bidirectional"))
    )
    (net (code "71") (name "unconnected-(Teensy-PadD-)") (class "Default")
      (node (ref "Teensy") (pin "D-") (pinfunction "D-_D-") (pintype "bidirectional"))
    )
    (net (code "72") (name "unconnected-(Teensy-PadLED)") (class "Default")
      (node (ref "Teensy") (pin "LED") (pinfunction "LED_LED") (pintype "bidirectional"))
    )
    (net (code "73") (name "unconnected-(Teensy-PadON{slash}OFF)") (class "Default")
      (node (ref "Teensy") (pin "ON/OFF") (pinfunction "ON/OFF_ON/OFF") (pintype "bidirectional"))
    )
    (net (code "74") (name "unconnected-(Teensy-PadPROGRAM)") (class "Default")
      (node (ref "Teensy") (pin "PROGRAM") (pinfunction "PROGRAM_PROGRAM") (pintype "bidirectional"))
    )
    (net (code "75") (name "unconnected-(Teensy-PadR+)") (class "Default")
      (node (ref "Teensy") (pin "R+") (pinfunction "R+_R+") (pintype "bidirectional"))
    )
    (net (code "76") (name "unconnected-(Teensy-PadR-)") (class "Default")
      (node (ref "Teensy") (pin "R-") (pinfunction "R-_R-") (pintype "bidirectional"))
    )
    (net (code "77") (name "unconnected-(Teensy-PadT+)") (class "Default")
      (node (ref "Teensy") (pin "T+") (pinfunction "T+_T+") (pintype "bidirectional"))
    )
    (net (code "78") (name "unconnected-(Teensy-PadT-)") (class "Default")
      (node (ref "Teensy") (pin "T-") (pinfunction "T-_T-") (pintype "bidirectional"))
    )
    (net (code "79") (name "unconnected-(Teensy-PadVBAT)") (class "Default")
      (node (ref "Teensy") (pin "VBAT") (pinfunction "VBAT_VBAT") (pintype "passive"))
    )
    (net (code "80") (name "unconnected-(Teensy-PadVUSB)") (class "Default")
      (node (ref "Teensy") (pin "VUSB") (pinfunction "VUSB_VUSB") (pintype "passive"))
    )
    (net (code "81") (name "unconnected-(Teensy-USB_GND-PadUSB_GND1)") (class "Default")
      (node (ref "Teensy") (pin "USB_GND1") (pinfunction "USB_GND_USB_GND1") (pintype "power_in"))
    )
    (net (code "82") (name "unconnected-(Teensy-USB_GND-PadUSB_GND2)") (class "Default")
      (node (ref "Teensy") (pin "USB_GND2") (pinfunction "USB_GND_USB_GND2") (pintype "power_in"))
    )
  )
)
